# door_module_a.net
KiCad netlist of a schematic drawn in EAGLE
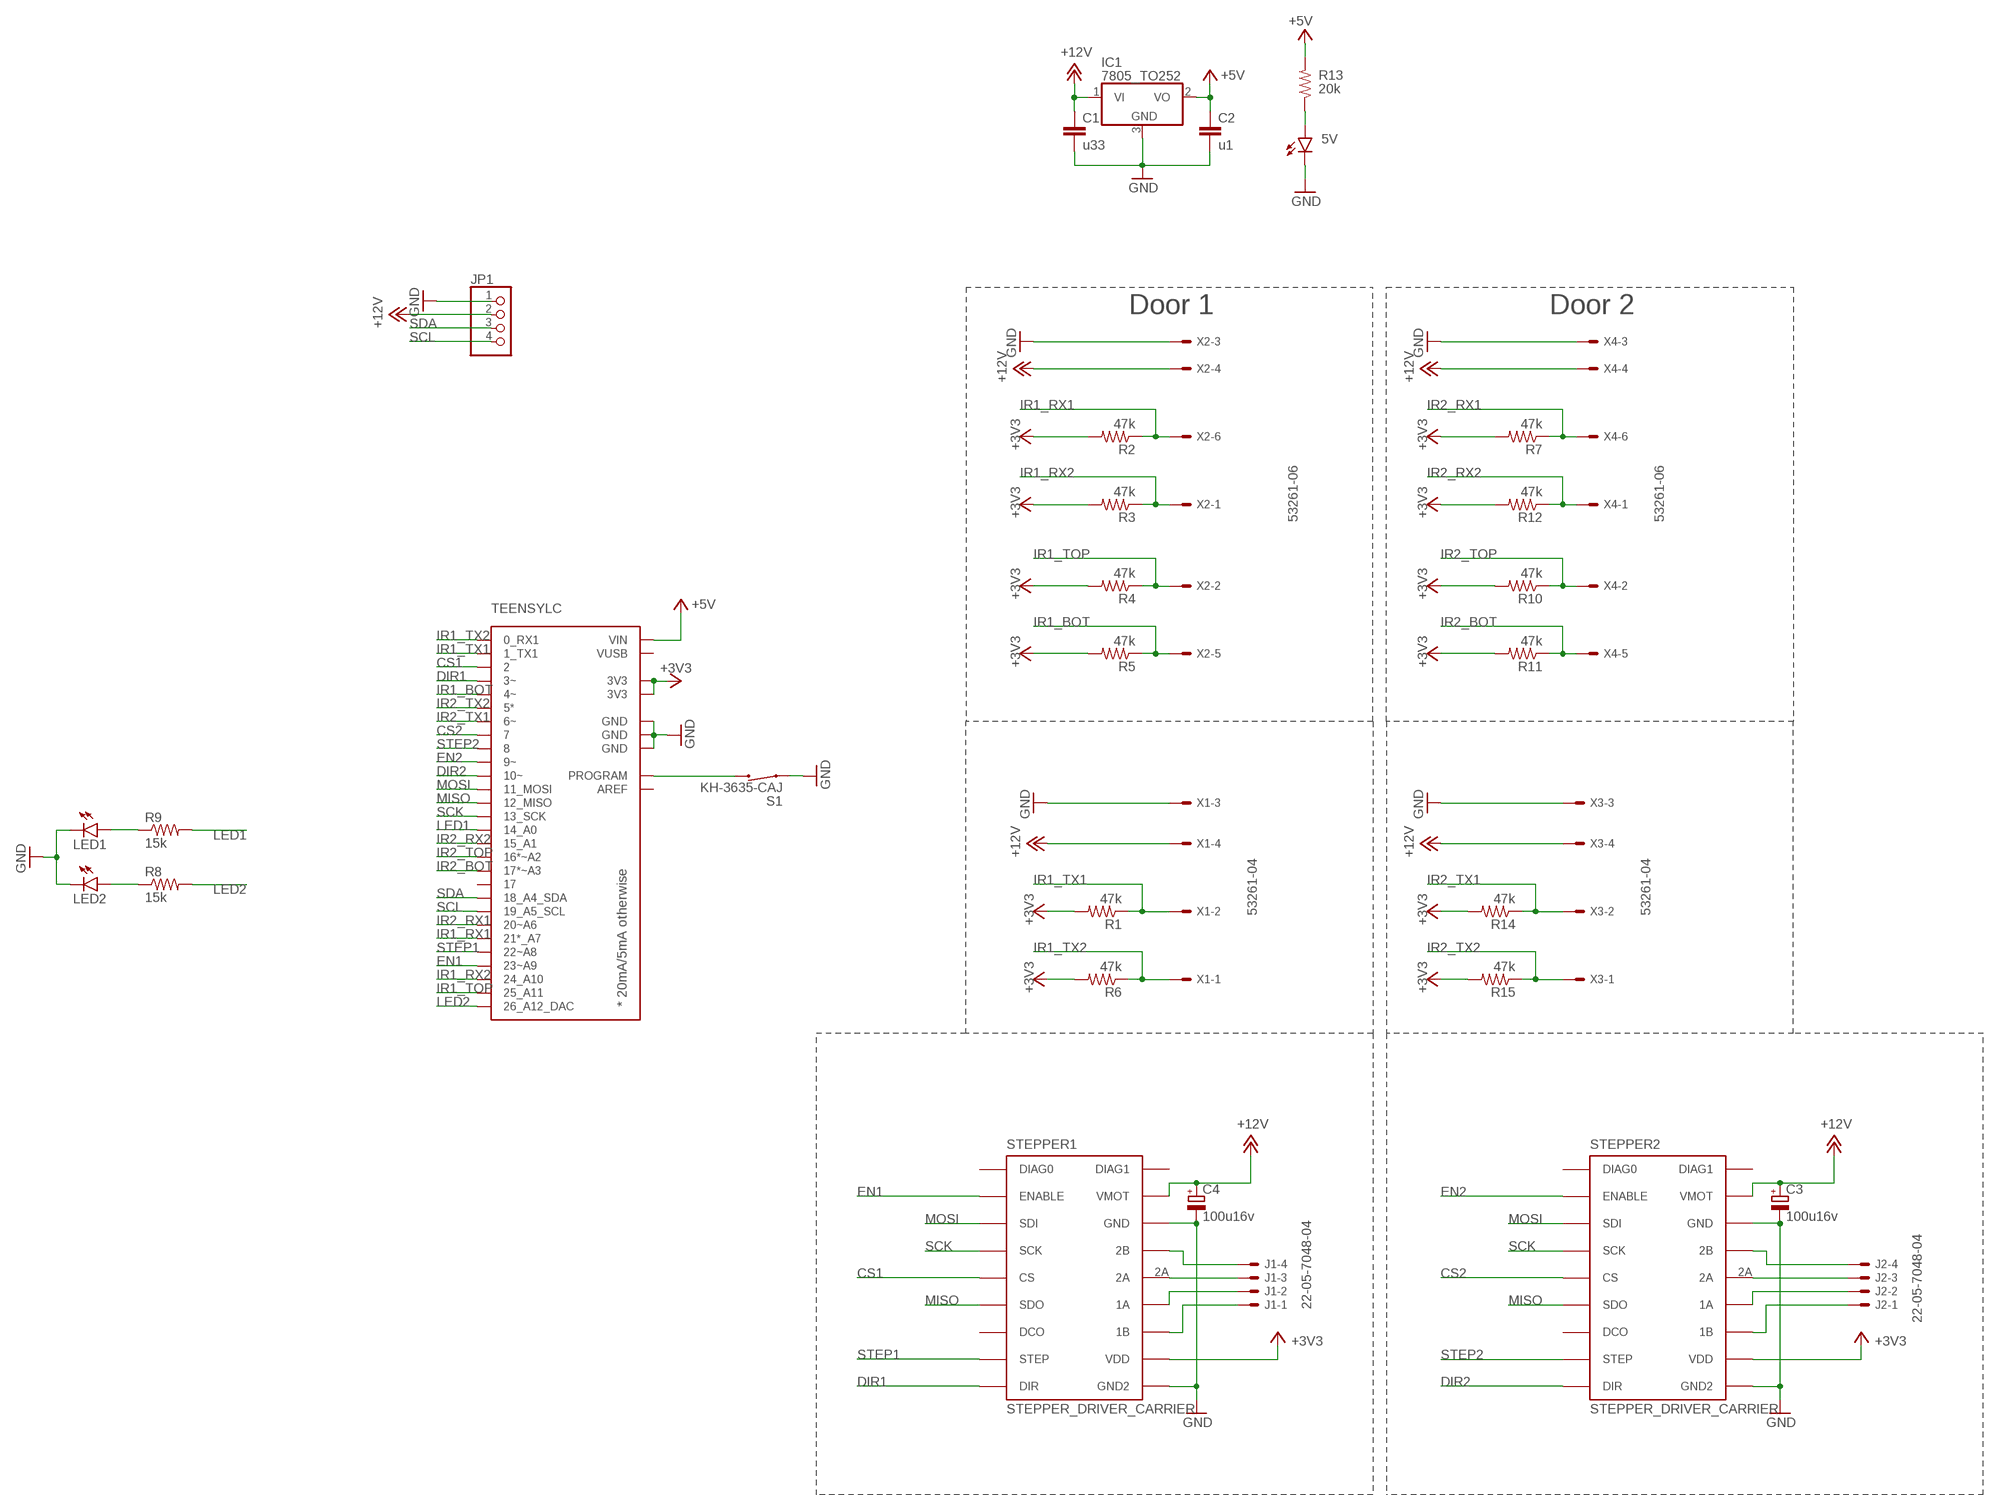
[diagram p0: schematic, sheet 1]

(export (version "E")
  (design (tool "Eeschema 10.0.6"))
  (components
    (comp (ref "5V")
      (value "LEDCHIPLED_0805")
      (footprint "eagle-import:CHIPLED_0805")
      (libsource (lib "eagle-import") (part "LEDCHIPLED_0805"))
    )
    (comp (ref "C1")
      (value "u33")
      (footprint "eagle-import:C0805")
      (libsource (lib "eagle-import") (part "C-EUC0805"))
    )
    (comp (ref "C2")
      (value "u1")
      (footprint "eagle-import:C0805")
      (libsource (lib "eagle-import") (part "C-EUC0805"))
    )
    (comp (ref "C3")
      (value "100u16v")
      (footprint "eagle-import:SMC_C")
      (libsource (lib "eagle-import") (part "CPOL-EUSMCC"))
    )
    (comp (ref "C4")
      (value "100u16v")
      (footprint "eagle-import:SMC_C")
      (libsource (lib "eagle-import") (part "CPOL-EUSMCC"))
    )
    (comp (ref "IC1")
      (value "7805_TO252")
      (footprint "eagle-import:TO252")
      (libsource (lib "eagle-import") (part "7805_TO252"))
    )
    (comp (ref "J1")
      (value "22-05-7048-04")
      (footprint "eagle-import:7395-04")
      (fields (field (name "MF") "MOLEX"))
      (libsource (lib "eagle-import") (part "22-?-0405-7048"))
    )
    (comp (ref "J2")
      (value "22-05-7048-04")
      (footprint "eagle-import:7395-04")
      (fields (field (name "MF") "MOLEX"))
      (libsource (lib "eagle-import") (part "22-?-0405-7048"))
    )
    (comp (ref "JP1")
      (value "PINHD-1X4")
      (footprint "eagle-import:1X04")
      (libsource (lib "eagle-import") (part "PINHD-1X4"))
    )
    (comp (ref "LED1")
      (value "LEDCHIPLED_0805")
      (footprint "eagle-import:CHIPLED_0805")
      (libsource (lib "eagle-import") (part "LEDCHIPLED_0805"))
    )
    (comp (ref "LED2")
      (value "LEDCHIPLED_0805")
      (footprint "eagle-import:CHIPLED_0805")
      (libsource (lib "eagle-import") (part "LEDCHIPLED_0805"))
    )
    (comp (ref "R1")
      (value "47k")
      (footprint "eagle-import:R0805")
      (libsource (lib "eagle-import") (part "R-US_R0805"))
    )
    (comp (ref "R2")
      (value "47k")
      (footprint "eagle-import:R0805")
      (libsource (lib "eagle-import") (part "R-US_R0805"))
    )
    (comp (ref "R3")
      (value "47k")
      (footprint "eagle-import:R0805")
      (libsource (lib "eagle-import") (part "R-US_R0805"))
    )
    (comp (ref "R4")
      (value "47k")
      (footprint "eagle-import:R0805")
      (libsource (lib "eagle-import") (part "R-US_R0805"))
    )
    (comp (ref "R5")
      (value "47k")
      (footprint "eagle-import:R0805")
      (libsource (lib "eagle-import") (part "R-US_R0805"))
    )
    (comp (ref "R6")
      (value "47k")
      (footprint "eagle-import:R0805")
      (libsource (lib "eagle-import") (part "R-US_R0805"))
    )
    (comp (ref "R7")
      (value "47k")
      (footprint "eagle-import:R0805")
      (libsource (lib "eagle-import") (part "R-US_R0805"))
    )
    (comp (ref "R8")
      (value "15k")
      (footprint "eagle-import:R0805")
      (libsource (lib "eagle-import") (part "R-US_R0805"))
    )
    (comp (ref "R9")
      (value "15k")
      (footprint "eagle-import:R0805")
      (libsource (lib "eagle-import") (part "R-US_R0805"))
    )
    (comp (ref "R10")
      (value "47k")
      (footprint "eagle-import:R0805")
      (libsource (lib "eagle-import") (part "R-US_R0805"))
    )
    (comp (ref "R11")
      (value "47k")
      (footprint "eagle-import:R0805")
      (libsource (lib "eagle-import") (part "R-US_R0805"))
    )
    (comp (ref "R12")
      (value "47k")
      (footprint "eagle-import:R0805")
      (libsource (lib "eagle-import") (part "R-US_R0805"))
    )
    (comp (ref "R13")
      (value "20k")
      (footprint "eagle-import:R0805")
      (libsource (lib "eagle-import") (part "R-US_R0805"))
    )
    (comp (ref "R14")
      (value "47k")
      (footprint "eagle-import:R0805")
      (libsource (lib "eagle-import") (part "R-US_R0805"))
    )
    (comp (ref "R15")
      (value "47k")
      (footprint "eagle-import:R0805")
      (libsource (lib "eagle-import") (part "R-US_R0805"))
    )
    (comp (ref "S1")
      (value "KH-3635-CAJ")
      (footprint "eagle-import:KH-3635-CAJ")
      (libsource (lib "eagle-import") (part "KH-3635-CAJ"))
    )
    (comp (ref "STEPPER1")
      (value "STEPPER_DRIVER_CARRIER")
      (footprint "eagle-import:TMC2130_CARRIER")
      (libsource (lib "eagle-import") (part "STEPPER_DRIVER_CARRIER"))
    )
    (comp (ref "STEPPER2")
      (value "STEPPER_DRIVER_CARRIER")
      (footprint "eagle-import:TMC2130_CARRIER")
      (libsource (lib "eagle-import") (part "STEPPER_DRIVER_CARRIER"))
    )
    (comp (ref "TEENSYLC")
      (value "TEENSYLC")
      (footprint "eagle-import:TEENSYLC")
      (libsource (lib "eagle-import") (part "TEENSYLC"))
    )
    (comp (ref "X1")
      (value "53261-04")
      (footprint "eagle-import:53261-04")
      (fields (field (name "MF") "MOLEX"))
      (libsource (lib "eagle-import") (part "53?-04261"))
    )
    (comp (ref "X2")
      (value "53261-06")
      (footprint "eagle-import:53261-06")
      (fields (field (name "MF") "MOLEX"))
      (libsource (lib "eagle-import") (part "53?-06261"))
    )
    (comp (ref "X3")
      (value "53261-04")
      (footprint "eagle-import:53261-04")
      (fields (field (name "MF") "MOLEX"))
      (libsource (lib "eagle-import") (part "53?-04261"))
    )
    (comp (ref "X4")
      (value "53261-06")
      (footprint "eagle-import:53261-06")
      (fields (field (name "MF") "MOLEX"))
      (libsource (lib "eagle-import") (part "53?-06261"))
    )
  )
  (nets
    (net (code "1") (name "+3V3") (class "Default")
      (node (ref "R1") (pin "2") (pinfunction "2_2") (pintype "passive"))
      (node (ref "R10") (pin "2") (pinfunction "2_2") (pintype "passive"))
      (node (ref "R11") (pin "2") (pinfunction "2_2") (pintype "passive"))
      (node (ref "R12") (pin "2") (pinfunction "2_2") (pintype "passive"))
      (node (ref "R14") (pin "2") (pinfunction "2_2") (pintype "passive"))
      (node (ref "R15") (pin "2") (pinfunction "2_2") (pintype "passive"))
      (node (ref "R2") (pin "2") (pinfunction "2_2") (pintype "passive"))
      (node (ref "R3") (pin "2") (pinfunction "2_2") (pintype "passive"))
      (node (ref "R4") (pin "2") (pinfunction "2_2") (pintype "passive"))
      (node (ref "R5") (pin "2") (pinfunction "2_2") (pintype "passive"))
      (node (ref "R6") (pin "2") (pinfunction "2_2") (pintype "passive"))
      (node (ref "R7") (pin "2") (pinfunction "2_2") (pintype "passive"))
      (node (ref "STEPPER1") (pin "VIO") (pinfunction "VDD_VIO") (pintype "bidirectional"))
      (node (ref "STEPPER2") (pin "VIO") (pinfunction "VDD_VIO") (pintype "bidirectional"))
      (node (ref "TEENSYLC") (pin "3V3") (pinfunction "3V3_3V3") (pintype "bidirectional"))
      (node (ref "TEENSYLC") (pin "3V3@2") (pinfunction "3V3_3V3@2") (pintype "bidirectional"))
    )
    (net (code "2") (name "+5V") (class "Default")
      (node (ref "C2") (pin "1") (pinfunction "1_1") (pintype "passive"))
      (node (ref "IC1") (pin "2") (pinfunction "VO_2") (pintype "passive"))
      (node (ref "R13") (pin "2") (pinfunction "2_2") (pintype "passive"))
      (node (ref "TEENSYLC") (pin "VIN") (pinfunction "VIN_VIN") (pintype "bidirectional"))
    )
    (net (code "3") (name "+12V") (class "Default")
      (node (ref "C1") (pin "1") (pinfunction "1_1") (pintype "passive"))
      (node (ref "C3") (pin "+") (pinfunction "+_+") (pintype "passive"))
      (node (ref "C4") (pin "+") (pinfunction "+_+") (pintype "passive"))
      (node (ref "IC1") (pin "1") (pinfunction "VI_1") (pintype "input"))
      (node (ref "JP1") (pin "2") (pinfunction "2_2") (pintype "passive"))
      (node (ref "STEPPER1") (pin "VMOT") (pinfunction "VMOT_VMOT") (pintype "power_in"))
      (node (ref "STEPPER2") (pin "VMOT") (pinfunction "VMOT_VMOT") (pintype "power_in"))
      (node (ref "X1") (pin "4") (pinfunction "S_4") (pintype "passive"))
      (node (ref "X2") (pin "4") (pinfunction "S_4") (pintype "passive"))
      (node (ref "X3") (pin "4") (pinfunction "S_4") (pintype "passive"))
      (node (ref "X4") (pin "4") (pinfunction "S_4") (pintype "passive"))
    )
    (net (code "4") (name "/CS1") (class "Default")
      (node (ref "STEPPER1") (pin "CS/CFG3") (pinfunction "CS_CS/CFG3") (pintype "input"))
      (node (ref "TEENSYLC") (pin "2") (pinfunction "2_2") (pintype "bidirectional"))
    )
    (net (code "5") (name "/CS2") (class "Default")
      (node (ref "STEPPER2") (pin "CS/CFG3") (pinfunction "CS_CS/CFG3") (pintype "input"))
      (node (ref "TEENSYLC") (pin "7") (pinfunction "7_7") (pintype "bidirectional"))
    )
    (net (code "6") (name "/DIR1") (class "Default")
      (node (ref "STEPPER1") (pin "DIR") (pinfunction "DIR_DIR") (pintype "input"))
      (node (ref "TEENSYLC") (pin "3") (pinfunction "3~{}_3") (pintype "bidirectional"))
    )
    (net (code "7") (name "/DIR2") (class "Default")
      (node (ref "STEPPER2") (pin "DIR") (pinfunction "DIR_DIR") (pintype "input"))
      (node (ref "TEENSYLC") (pin "10") (pinfunction "10~{}_10") (pintype "bidirectional"))
    )
    (net (code "8") (name "/EN1") (class "Default")
      (node (ref "STEPPER1") (pin "ENABLE") (pinfunction "ENABLE_ENABLE") (pintype "input"))
      (node (ref "TEENSYLC") (pin "23") (pinfunction "23~{A9}_23") (pintype "bidirectional"))
    )
    (net (code "9") (name "/EN2") (class "Default")
      (node (ref "STEPPER2") (pin "ENABLE") (pinfunction "ENABLE_ENABLE") (pintype "input"))
      (node (ref "TEENSYLC") (pin "9") (pinfunction "9~{}_9") (pintype "bidirectional"))
    )
    (net (code "10") (name "/IR1_BOT") (class "Default")
      (node (ref "R5") (pin "1") (pinfunction "1_1") (pintype "passive"))
      (node (ref "TEENSYLC") (pin "4") (pinfunction "4~{}_4") (pintype "bidirectional"))
      (node (ref "X2") (pin "5") (pinfunction "S_5") (pintype "passive"))
    )
    (net (code "11") (name "/IR1_RX1") (class "Default")
      (node (ref "R2") (pin "1") (pinfunction "1_1") (pintype "passive"))
      (node (ref "TEENSYLC") (pin "21") (pinfunction "21*_A7_21") (pintype "bidirectional"))
      (node (ref "X2") (pin "6") (pinfunction "S_6") (pintype "passive"))
    )
    (net (code "12") (name "/IR1_RX2") (class "Default")
      (node (ref "R3") (pin "1") (pinfunction "1_1") (pintype "passive"))
      (node (ref "TEENSYLC") (pin "24") (pinfunction "24_A10_24") (pintype "bidirectional"))
      (node (ref "X2") (pin "1") (pinfunction "S_1") (pintype "passive"))
    )
    (net (code "13") (name "/IR1_TOP") (class "Default")
      (node (ref "R4") (pin "1") (pinfunction "1_1") (pintype "passive"))
      (node (ref "TEENSYLC") (pin "25") (pinfunction "25_A11_25") (pintype "bidirectional"))
      (node (ref "X2") (pin "2") (pinfunction "S_2") (pintype "passive"))
    )
    (net (code "14") (name "/IR1_TX1") (class "Default")
      (node (ref "R1") (pin "1") (pinfunction "1_1") (pintype "passive"))
      (node (ref "TEENSYLC") (pin "1") (pinfunction "1_TX1_1") (pintype "bidirectional"))
      (node (ref "X1") (pin "2") (pinfunction "S_2") (pintype "passive"))
    )
    (net (code "15") (name "/IR1_TX2") (class "Default")
      (node (ref "R6") (pin "1") (pinfunction "1_1") (pintype "passive"))
      (node (ref "TEENSYLC") (pin "0") (pinfunction "0_RX1_0") (pintype "bidirectional"))
      (node (ref "X1") (pin "1") (pinfunction "S_1") (pintype "passive"))
    )
    (net (code "16") (name "/IR2_BOT") (class "Default")
      (node (ref "R11") (pin "1") (pinfunction "1_1") (pintype "passive"))
      (node (ref "TEENSYLC") (pin "17") (pinfunction "17*~{A3}_17") (pintype "bidirectional"))
      (node (ref "X4") (pin "5") (pinfunction "S_5") (pintype "passive"))
    )
    (net (code "17") (name "/IR2_RX1") (class "Default")
      (node (ref "R7") (pin "1") (pinfunction "1_1") (pintype "passive"))
      (node (ref "TEENSYLC") (pin "20") (pinfunction "20~{A6}_20") (pintype "bidirectional"))
      (node (ref "X4") (pin "6") (pinfunction "S_6") (pintype "passive"))
    )
    (net (code "18") (name "/IR2_RX2") (class "Default")
      (node (ref "R12") (pin "1") (pinfunction "1_1") (pintype "passive"))
      (node (ref "TEENSYLC") (pin "15") (pinfunction "15_A1_15") (pintype "bidirectional"))
      (node (ref "X4") (pin "1") (pinfunction "S_1") (pintype "passive"))
    )
    (net (code "19") (name "/IR2_TOP") (class "Default")
      (node (ref "R10") (pin "1") (pinfunction "1_1") (pintype "passive"))
      (node (ref "TEENSYLC") (pin "16") (pinfunction "16*~{A2}_16") (pintype "bidirectional"))
      (node (ref "X4") (pin "2") (pinfunction "S_2") (pintype "passive"))
    )
    (net (code "20") (name "/IR2_TX1") (class "Default")
      (node (ref "R14") (pin "1") (pinfunction "1_1") (pintype "passive"))
      (node (ref "TEENSYLC") (pin "6") (pinfunction "6~{}_6") (pintype "bidirectional"))
      (node (ref "X3") (pin "2") (pinfunction "S_2") (pintype "passive"))
    )
    (net (code "21") (name "/IR2_TX2") (class "Default")
      (node (ref "R15") (pin "1") (pinfunction "1_1") (pintype "passive"))
      (node (ref "TEENSYLC") (pin "5") (pinfunction "5*_5") (pintype "bidirectional"))
      (node (ref "X3") (pin "1") (pinfunction "S_1") (pintype "passive"))
    )
    (net (code "22") (name "/LED1") (class "Default")
      (node (ref "R9") (pin "2") (pinfunction "2_2") (pintype "passive"))
      (node (ref "TEENSYLC") (pin "14") (pinfunction "14_A0_14") (pintype "bidirectional"))
    )
    (net (code "23") (name "/LED2") (class "Default")
      (node (ref "R8") (pin "2") (pinfunction "2_2") (pintype "passive"))
      (node (ref "TEENSYLC") (pin "26") (pinfunction "26_A12_DAC_26") (pintype "bidirectional"))
    )
    (net (code "24") (name "/MISO") (class "Default")
      (node (ref "STEPPER1") (pin "SDO/CFG0") (pinfunction "SDO_SDO/CFG0") (pintype "input"))
      (node (ref "STEPPER2") (pin "SDO/CFG0") (pinfunction "SDO_SDO/CFG0") (pintype "input"))
      (node (ref "TEENSYLC") (pin "12") (pinfunction "12_MISO_12") (pintype "bidirectional"))
    )
    (net (code "25") (name "/MOSI") (class "Default")
      (node (ref "STEPPER1") (pin "SDI/CFG1") (pinfunction "SDI_SDI/CFG1") (pintype "input"))
      (node (ref "STEPPER2") (pin "SDI/CFG1") (pinfunction "SDI_SDI/CFG1") (pintype "input"))
      (node (ref "TEENSYLC") (pin "11") (pinfunction "11_MOSI_11") (pintype "bidirectional"))
    )
    (net (code "26") (name "/SCK") (class "Default")
      (node (ref "STEPPER1") (pin "SCK/CFG2") (pinfunction "SCK_SCK/CFG2") (pintype "input"))
      (node (ref "STEPPER2") (pin "SCK/CFG2") (pinfunction "SCK_SCK/CFG2") (pintype "input"))
      (node (ref "TEENSYLC") (pin "13") (pinfunction "13_SCK_13") (pintype "bidirectional"))
    )
    (net (code "27") (name "/SCL") (class "Default")
      (node (ref "JP1") (pin "4") (pinfunction "4_4") (pintype "passive"))
      (node (ref "TEENSYLC") (pin "19") (pinfunction "19_A5_SCL_19") (pintype "bidirectional"))
    )
    (net (code "28") (name "/SDA") (class "Default")
      (node (ref "JP1") (pin "3") (pinfunction "3_3") (pintype "passive"))
      (node (ref "TEENSYLC") (pin "18") (pinfunction "18_A4_SDA_18") (pintype "bidirectional"))
    )
    (net (code "29") (name "/STEP1") (class "Default")
      (node (ref "STEPPER1") (pin "STEP") (pinfunction "STEP_STEP") (pintype "input"))
      (node (ref "TEENSYLC") (pin "22") (pinfunction "22~{A8}_22") (pintype "bidirectional"))
    )
    (net (code "30") (name "/STEP2") (class "Default")
      (node (ref "STEPPER2") (pin "STEP") (pinfunction "STEP_STEP") (pintype "input"))
      (node (ref "TEENSYLC") (pin "8") (pinfunction "8_8") (pintype "bidirectional"))
    )
    (net (code "31") (name "GND") (class "Default")
      (node (ref "5V") (pin "C") (pinfunction "C_C") (pintype "passive"))
      (node (ref "C1") (pin "2") (pinfunction "2_2") (pintype "passive"))
      (node (ref "C2") (pin "2") (pinfunction "2_2") (pintype "passive"))
      (node (ref "C3") (pin "-") (pinfunction "-_-") (pintype "passive"))
      (node (ref "C4") (pin "-") (pinfunction "-_-") (pintype "passive"))
      (node (ref "IC1") (pin "3") (pinfunction "GND_3") (pintype "passive"))
      (node (ref "JP1") (pin "1") (pinfunction "1_1") (pintype "passive"))
      (node (ref "LED1") (pin "C") (pinfunction "C_C") (pintype "passive"))
      (node (ref "LED2") (pin "C") (pinfunction "C_C") (pintype "passive"))
      (node (ref "S1") (pin "P$1") (pinfunction "1_P$1") (pintype "passive"))
      (node (ref "STEPPER1") (pin "GND") (pinfunction "GND_GND") (pintype "power_in"))
      (node (ref "STEPPER1") (pin "GND2") (pinfunction "GND2_GND2") (pintype "power_in"))
      (node (ref "STEPPER2") (pin "GND") (pinfunction "GND_GND") (pintype "power_in"))
      (node (ref "STEPPER2") (pin "GND2") (pinfunction "GND2_GND2") (pintype "power_in"))
      (node (ref "TEENSYLC") (pin "GND") (pinfunction "GND_GND") (pintype "bidirectional"))
      (node (ref "TEENSYLC") (pin "GND@1") (pinfunction "GND_GND@1") (pintype "bidirectional"))
      (node (ref "TEENSYLC") (pin "GND@2") (pinfunction "GND_GND@2") (pintype "bidirectional"))
      (node (ref "X1") (pin "3") (pinfunction "S_3") (pintype "passive"))
      (node (ref "X2") (pin "3") (pinfunction "S_3") (pintype "passive"))
      (node (ref "X3") (pin "3") (pinfunction "S_3") (pintype "passive"))
      (node (ref "X4") (pin "3") (pinfunction "S_3") (pintype "passive"))
    )
    (net (code "32") (name "Net-(5V-PadA)") (class "Default")
      (node (ref "5V") (pin "A") (pinfunction "A_A") (pintype "passive"))
      (node (ref "R13") (pin "1") (pinfunction "1_1") (pintype "passive"))
    )
    (net (code "33") (name "Net-(J1A-S)") (class "Default")
      (node (ref "J1") (pin "1") (pinfunction "S_1") (pintype "passive"))
      (node (ref "STEPPER1") (pin "1B") (pinfunction "1B_1B") (pintype "output"))
    )
    (net (code "34") (name "Net-(J1B-S)") (class "Default")
      (node (ref "J1") (pin "2") (pinfunction "S_2") (pintype "passive"))
      (node (ref "STEPPER1") (pin "1A") (pinfunction "1A_1A") (pintype "output"))
    )
    (net (code "35") (name "Net-(J1C-S)") (class "Default")
      (node (ref "J1") (pin "3") (pinfunction "S_3") (pintype "passive"))
      (node (ref "STEPPER1") (pin "2A") (pinfunction "2A_2A") (pintype "output"))
    )
    (net (code "36") (name "Net-(J1D-S)") (class "Default")
      (node (ref "J1") (pin "4") (pinfunction "S_4") (pintype "passive"))
      (node (ref "STEPPER1") (pin "2B") (pinfunction "2B_2B") (pintype "output"))
    )
    (net (code "37") (name "Net-(J2A-S)") (class "Default")
      (node (ref "J2") (pin "1") (pinfunction "S_1") (pintype "passive"))
      (node (ref "STEPPER2") (pin "1B") (pinfunction "1B_1B") (pintype "output"))
    )
    (net (code "38") (name "Net-(J2B-S)") (class "Default")
      (node (ref "J2") (pin "2") (pinfunction "S_2") (pintype "passive"))
      (node (ref "STEPPER2") (pin "1A") (pinfunction "1A_1A") (pintype "output"))
    )
    (net (code "39") (name "Net-(J2C-S)") (class "Default")
      (node (ref "J2") (pin "3") (pinfunction "S_3") (pintype "passive"))
      (node (ref "STEPPER2") (pin "2A") (pinfunction "2A_2A") (pintype "output"))
    )
    (net (code "40") (name "Net-(J2D-S)") (class "Default")
      (node (ref "J2") (pin "4") (pinfunction "S_4") (pintype "passive"))
      (node (ref "STEPPER2") (pin "2B") (pinfunction "2B_2B") (pintype "output"))
    )
    (net (code "41") (name "Net-(LED1-PadA)") (class "Default")
      (node (ref "LED1") (pin "A") (pinfunction "A_A") (pintype "passive"))
      (node (ref "R9") (pin "1") (pinfunction "1_1") (pintype "passive"))
    )
    (net (code "42") (name "Net-(LED2-PadA)") (class "Default")
      (node (ref "LED2") (pin "A") (pinfunction "A_A") (pintype "passive"))
      (node (ref "R8") (pin "1") (pinfunction "1_1") (pintype "passive"))
    )
    (net (code "43") (name "Net-(S1-2)") (class "Default")
      (node (ref "S1") (pin "P$2") (pinfunction "2_P$2") (pintype "passive"))
      (node (ref "TEENSYLC") (pin "PROG") (pinfunction "PROGRAM_PROG") (pintype "bidirectional"))
    )
    (net (code "44") (name "unconnected-(STEPPER1-PadDCO)") (class "Default")
      (node (ref "STEPPER1") (pin "DCO") (pinfunction "DCO_DCO") (pintype "input"))
    )
    (net (code "45") (name "unconnected-(STEPPER1-PadDIAG0)") (class "Default")
      (node (ref "STEPPER1") (pin "DIAG0") (pinfunction "DIAG0_DIAG0") (pintype "bidirectional"))
    )
    (net (code "46") (name "unconnected-(STEPPER1-PadDIAG1)") (class "Default")
      (node (ref "STEPPER1") (pin "DIAG1") (pinfunction "DIAG1_DIAG1") (pintype "bidirectional"))
    )
    (net (code "47") (name "unconnected-(STEPPER2-PadDCO)") (class "Default")
      (node (ref "STEPPER2") (pin "DCO") (pinfunction "DCO_DCO") (pintype "input"))
    )
    (net (code "48") (name "unconnected-(STEPPER2-PadDIAG0)") (class "Default")
      (node (ref "STEPPER2") (pin "DIAG0") (pinfunction "DIAG0_DIAG0") (pintype "bidirectional"))
    )
    (net (code "49") (name "unconnected-(STEPPER2-PadDIAG1)") (class "Default")
      (node (ref "STEPPER2") (pin "DIAG1") (pinfunction "DIAG1_DIAG1") (pintype "bidirectional"))
    )
    (net (code "50") (name "unconnected-(TEENSYLC-17-Pad17@VIN)") (class "Default")
      (node (ref "TEENSYLC") (pin "17@VIN") (pinfunction "17_17@VIN") (pintype "bidirectional"))
    )
    (net (code "51") (name "unconnected-(TEENSYLC-PadAREF)") (class "Default")
      (node (ref "TEENSYLC") (pin "AREF") (pinfunction "AREF_AREF") (pintype "bidirectional"))
    )
    (net (code "52") (name "unconnected-(TEENSYLC-PadVUSB)") (class "Default")
      (node (ref "TEENSYLC") (pin "VUSB") (pinfunction "VUSB_VUSB") (pintype "bidirectional"))
    )
  )
)
